# MODULO_LDR.net
KiCad netlist of a schematic drawn in EAGLE
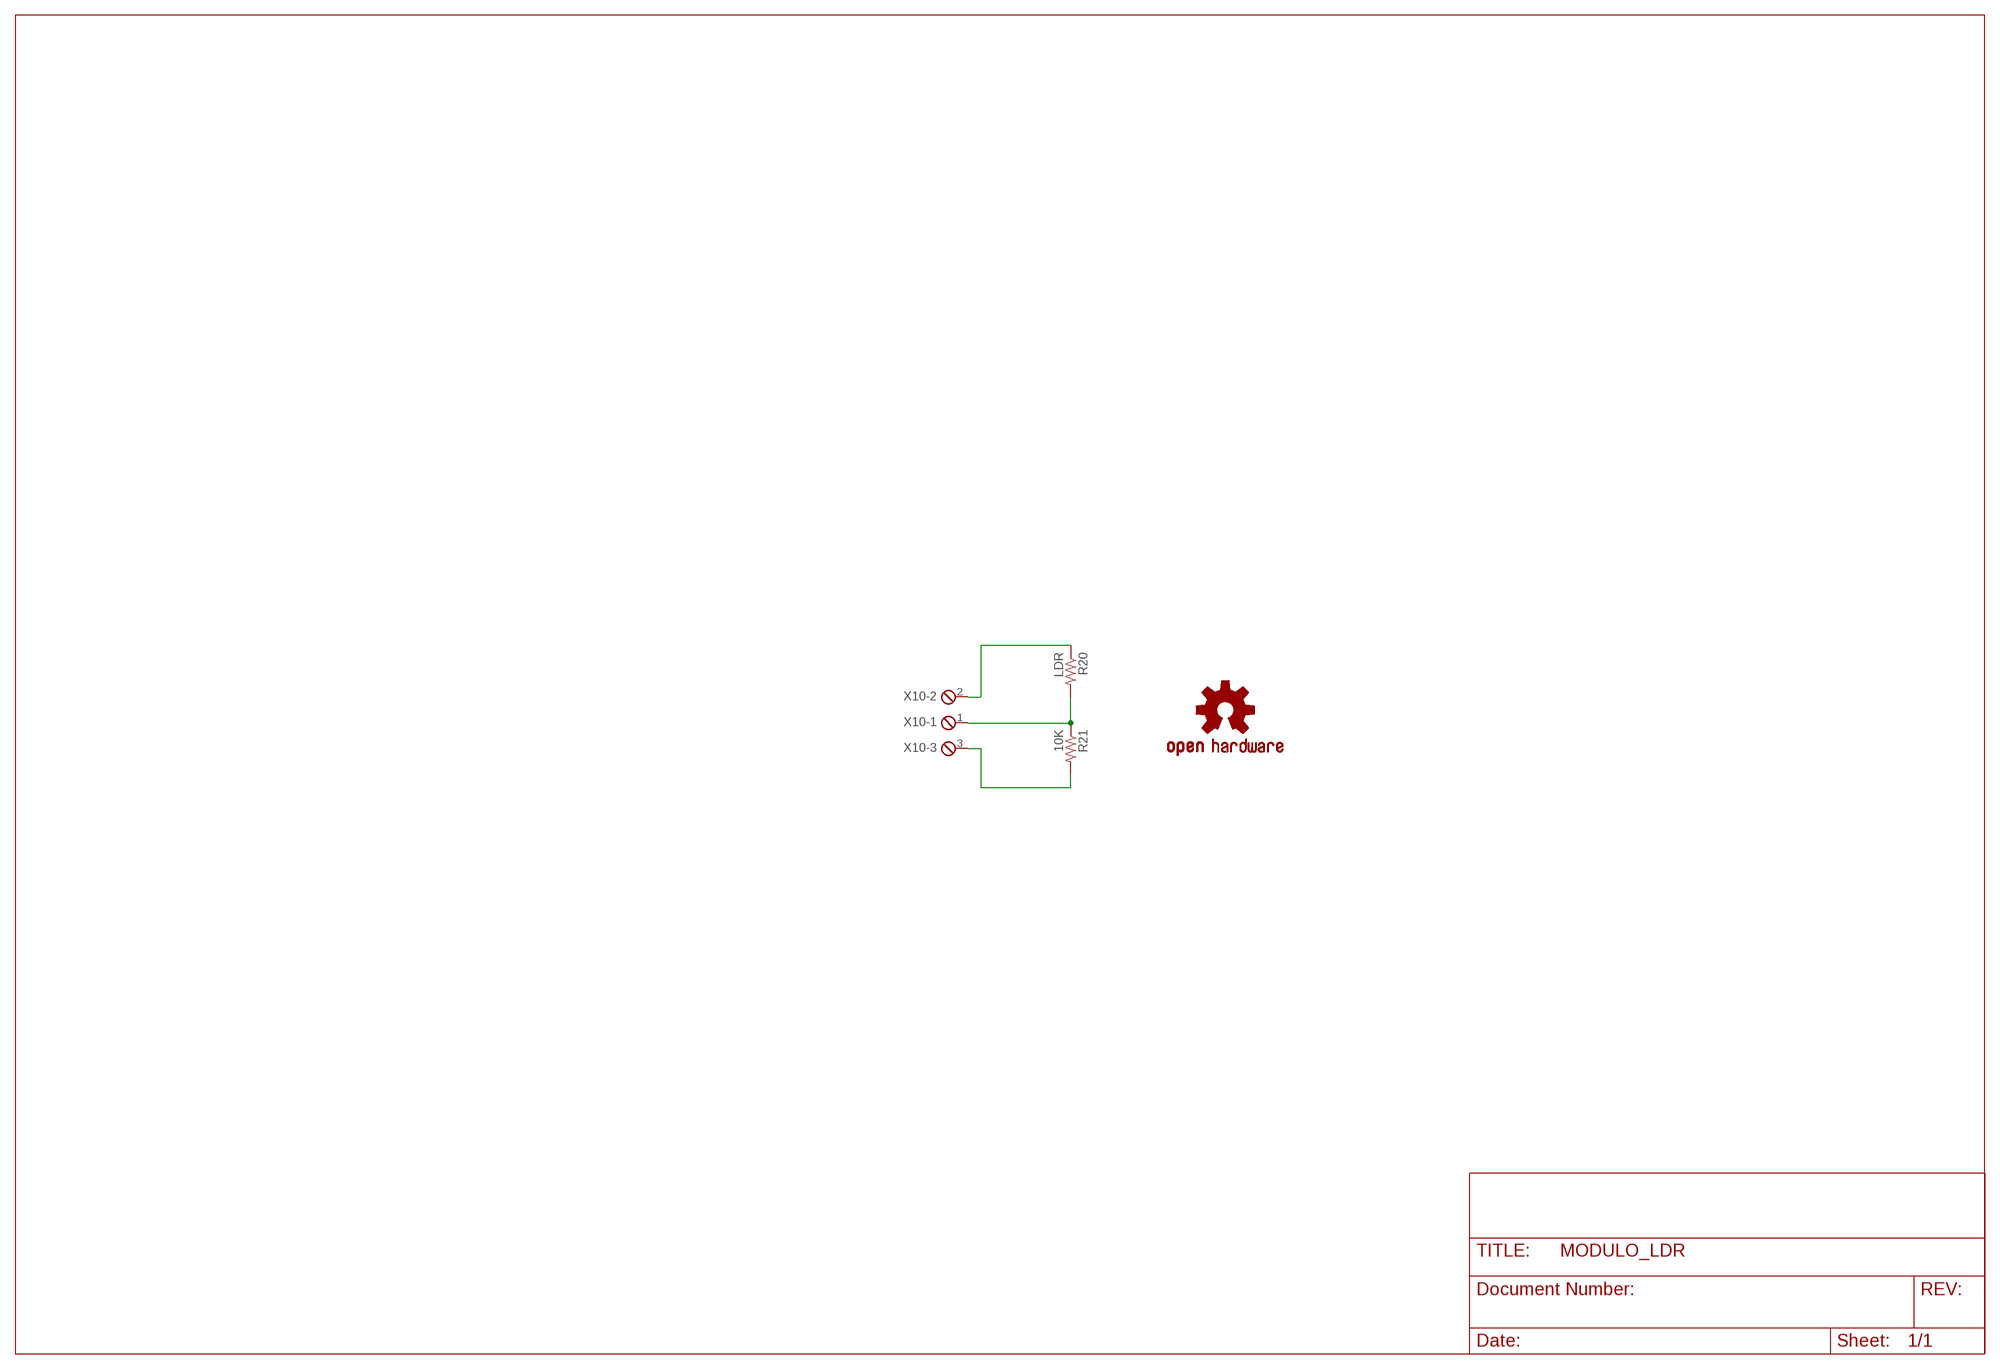
[diagram p0: schematic, sheet 1]

(export (version "E")
  (design (tool "Eeschema 10.0.6"))
  (components
    (comp (ref "LOGO1")
      (value "OSHW-LOGOS")
      (footprint "eagle-import:OSHW-LOGO-S")
      (libsource (lib "eagle-import") (part "OSHW-LOGOS"))
    )
    (comp (ref "R20")
      (value "LDR")
      (footprint "eagle-import:1_6W-RES")
      (libsource (lib "eagle-import") (part "RESISTORPTH-1/6W"))
    )
    (comp (ref "R21")
      (value "10K")
      (footprint "eagle-import:AXIAL-0.4")
      (libsource (lib "eagle-import") (part "RESISTORPTH-1/4W"))
    )
    (comp (ref "X10")
      (value "MPT3")
      (footprint "eagle-import:3POL254")
      (libsource (lib "eagle-import") (part "MPT3"))
    )
  )
  (nets
    (net (code "1") (name "Net-(R21-1)") (class "Default")
      (node (ref "R20") (pin "2") (pinfunction "2_2") (pintype "passive"))
      (node (ref "R21") (pin "P$1") (pinfunction "1_P$1") (pintype "passive"))
      (node (ref "X10") (pin "1") (pinfunction "1_1") (pintype "passive"))
    )
    (net (code "2") (name "Net-(R21-2)") (class "Default")
      (node (ref "R21") (pin "P$2") (pinfunction "2_P$2") (pintype "passive"))
      (node (ref "X10") (pin "3") (pinfunction "1_3") (pintype "passive"))
    )
    (net (code "3") (name "Net-(X10B-1)") (class "Default")
      (node (ref "R20") (pin "1") (pinfunction "1_1") (pintype "passive"))
      (node (ref "X10") (pin "2") (pinfunction "1_2") (pintype "passive"))
    )
  )
)
